# board_4_pg1.net
KiCad netlist of a schematic drawn in Altium Designer
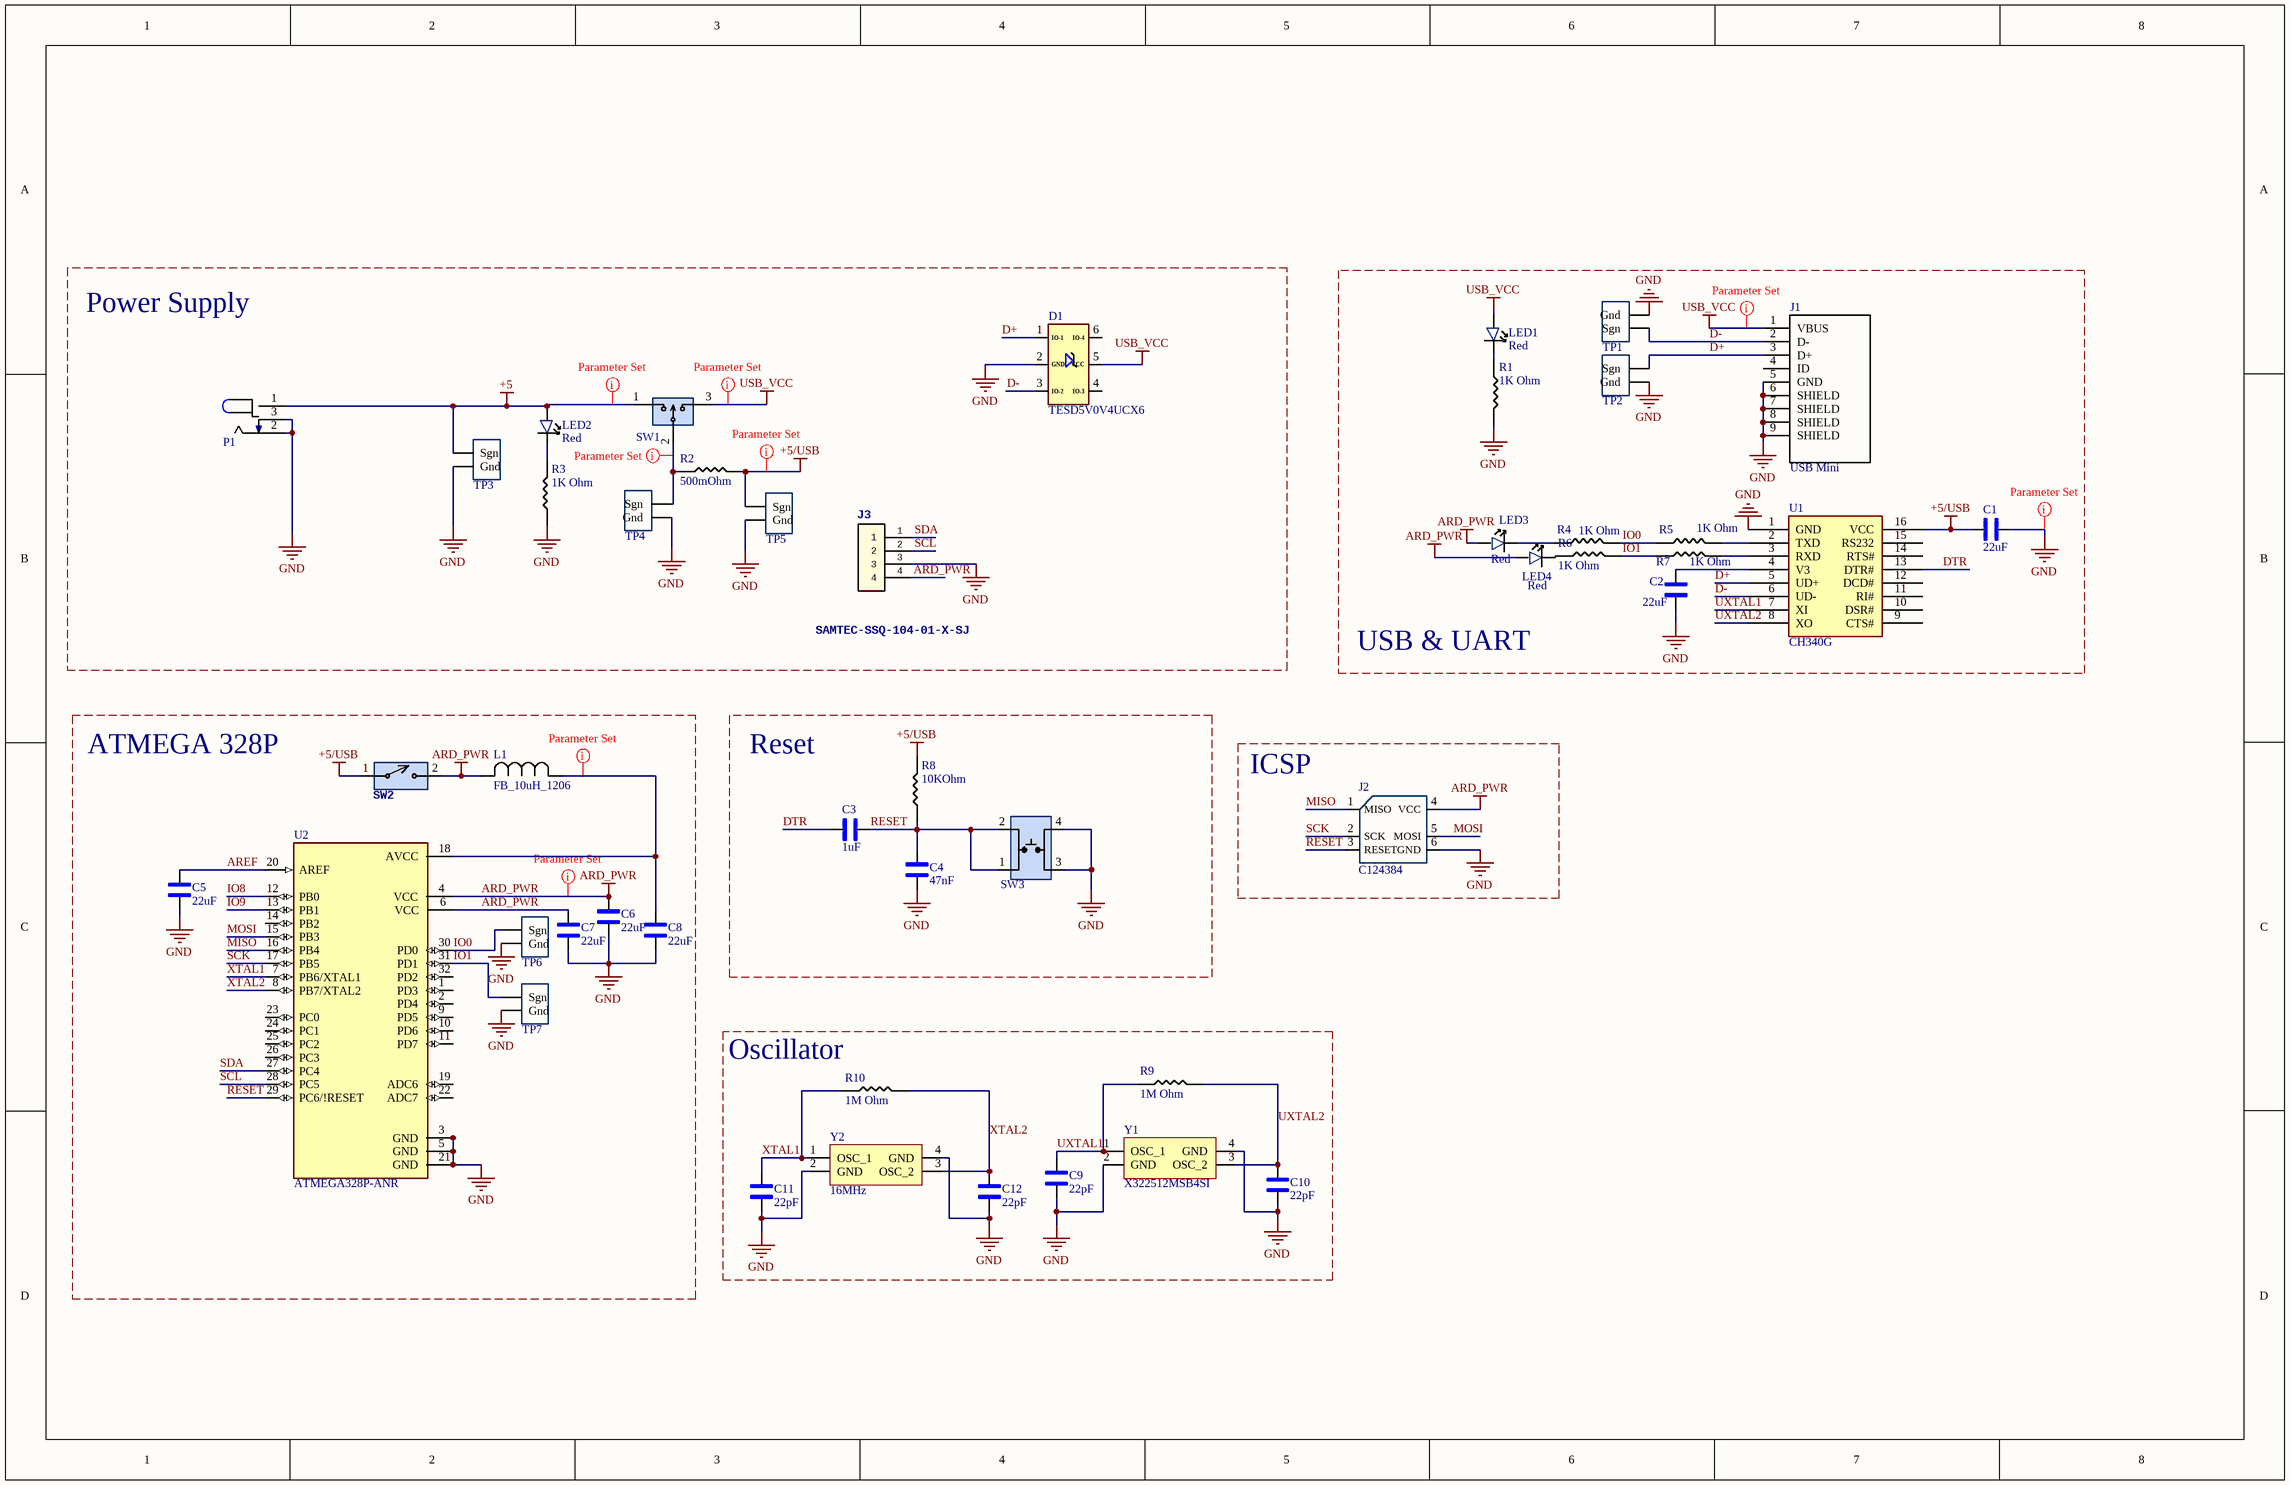
[diagram p0: board_4_pg1.SchDoc]

(export (version "E")
  (design (tool "Eeschema 10.0.6"))
  (components
    (comp (ref "C1")
      (value "22uF")
      (footprint "1206_Passive_Capacitor")
      (description "22uF ±10% 25V X5R 1206 Multilayer Ceramic Capacitors MLCC - SMD/SMT RoHS")
      (fields (field (name "MFR PART #") "CL31A226KAHNNNE") (field (name "LCSC PART#") "C12891"))
      (libsource (lib "ECEN5730Lib_2023_05_DS") (part "C_22uF_1206"))
    )
    (comp (ref "C2")
      (value "22uF")
      (footprint "1206_Passive_Capacitor")
      (description "22uF ±10% 25V X5R 1206 Multilayer Ceramic Capacitors MLCC - SMD/SMT RoHS")
      (fields (field (name "MFR PART #") "CL31A226KAHNNNE") (field (name "LCSC PART#") "C12891"))
      (libsource (lib "ECEN5730Lib_2023_05_DS") (part "C_22uF_1206"))
    )
    (comp (ref "C3")
      (value "1uF")
      (footprint "1206_Passive_Capacitor")
      (description "MULTILAYER CERAMIC CAPACITORS MLCC - SMD/SMT 1UF 50V 1206 ROHS")
      (fields (field (name "MFR PART #") "CL31B105KBHNNNE") (field (name "LCSC PART#") "C1848"))
      (libsource (lib "ECEN5730Lib_2023_05_DS") (part "C_1uF_1206"))
    )
    (comp (ref "C4")
      (value "47nF")
      (footprint "1206_Passive_Capacitor")
      (description "47nF ±5% 50V C0G 1206 Multilayer Ceramic Capacitors MLCC - SMD/SMT RoHS")
      (fields (field (name "LCSC PART#") "C21812") (field (name "MFR PART #") "GRM31M5C1H473JA01L"))
      (libsource (lib "ECEN5730Lib_2023_05_DS") (part "C_47nF_1206"))
    )
    (comp (ref "C5")
      (value "22uF")
      (footprint "1206_Passive_Capacitor")
      (description "22uF ±10% 25V X5R 1206 Multilayer Ceramic Capacitors MLCC - SMD/SMT RoHS")
      (fields (field (name "MFR PART #") "CL31A226KAHNNNE") (field (name "LCSC PART#") "C12891"))
      (libsource (lib "ECEN5730Lib_2023_05_DS") (part "C_22uF_1206"))
    )
    (comp (ref "C6")
      (value "22uF")
      (footprint "1206_Passive_Capacitor")
      (description "22uF ±10% 25V X5R 1206 Multilayer Ceramic Capacitors MLCC - SMD/SMT RoHS")
      (fields (field (name "MFR PART #") "CL31A226KAHNNNE") (field (name "LCSC PART#") "C12891"))
      (libsource (lib "ECEN5730Lib_2023_05_DS") (part "C_22uF_1206"))
    )
    (comp (ref "C7")
      (value "22uF")
      (footprint "1206_Passive_Capacitor")
      (description "22uF ±10% 25V X5R 1206 Multilayer Ceramic Capacitors MLCC - SMD/SMT RoHS")
      (fields (field (name "MFR PART #") "CL31A226KAHNNNE") (field (name "LCSC PART#") "C12891"))
      (libsource (lib "ECEN5730Lib_2023_05_DS") (part "C_22uF_1206"))
    )
    (comp (ref "C8")
      (value "22uF")
      (footprint "1206_Passive_Capacitor")
      (description "22uF ±10% 25V X5R 1206 Multilayer Ceramic Capacitors MLCC - SMD/SMT RoHS")
      (fields (field (name "MFR PART #") "CL31A226KAHNNNE") (field (name "LCSC PART#") "C12891"))
      (libsource (lib "ECEN5730Lib_2023_05_DS") (part "C_22uF_1206"))
    )
    (comp (ref "C9")
      (value "22pF")
      (footprint "1206_Passive_Capacitor")
      (description "22pF ±5% 1kV C0G 1206 Multilayer Ceramic Capacitors MLCC - SMD/SMT RoHS")
      (fields (field (name "LCSC PART#") "C107174") (field (name "MFR PART #") "CC1206JKNPOCBN220"))
      (libsource (lib "ECEN5730Lib_2023_05_DS") (part "C_22pF_1206"))
    )
    (comp (ref "C10")
      (value "22pF")
      (footprint "1206_Passive_Capacitor")
      (description "22pF ±5% 1kV C0G 1206 Multilayer Ceramic Capacitors MLCC - SMD/SMT RoHS")
      (fields (field (name "LCSC PART#") "C107174") (field (name "MFR PART #") "CC1206JKNPOCBN220"))
      (libsource (lib "ECEN5730Lib_2023_05_DS") (part "C_22pF_1206"))
    )
    (comp (ref "C11")
      (value "22pF")
      (footprint "1206_Passive_Capacitor")
      (description "22pF ±5% 1kV C0G 1206 Multilayer Ceramic Capacitors MLCC - SMD/SMT RoHS")
      (fields (field (name "LCSC PART#") "C107174") (field (name "MFR PART #") "CC1206JKNPOCBN220"))
      (libsource (lib "ECEN5730Lib_2023_05_DS") (part "C_22pF_1206"))
    )
    (comp (ref "C12")
      (value "22pF")
      (footprint "1206_Passive_Capacitor")
      (description "22pF ±5% 1kV C0G 1206 Multilayer Ceramic Capacitors MLCC - SMD/SMT RoHS")
      (fields (field (name "LCSC PART#") "C107174") (field (name "MFR PART #") "CC1206JKNPOCBN220"))
      (libsource (lib "ECEN5730Lib_2023_05_DS") (part "C_22pF_1206"))
    )
    (comp (ref "D1")
      (value "TESD5V0V4UCX6")
      (footprint "TVS - TESD")
      (description "TVS SOT-23 ROHS")
      (fields (field (name "LCSC PART#") "C5289077"))
      (libsource (lib "ECEN5730Lib_2023_05_DS_NEW") (part "D_TVS_Diode_TESD"))
    )
    (comp (ref "J1")
      (value "USB Mini")
      (footprint "USB_MINI_B")
      (description "Through Hole USB Connectors RoHS")
      (fields (field (name "LCSC PART#") "C46398") (field (name "MFR PART #") "920-462A2021D10102"))
      (libsource (lib "ECEN5730Lib_2023_05_DS") (part "J_USB_B_Mini"))
    )
    (comp (ref "J2")
      (value "NRPN032PAEN-RC")
      (footprint "ICSP")
      (description "Connector Header Through Hole 6 position 0.079\" (2.00mm)")
      (fields (field (name "LCSC PART#") "C124384"))
      (libsource (lib "ECEN5730Lib_2023_05_DS") (part "J_ICSP"))
    )
    (comp (ref "J3")
      (value "SAMTEC-SSQ-104-01-X-SJ")
      (footprint "JF-4_SSQ-104-01-X-S")
      (fields (field (name "MFR PART #") "SSQ-104-01-X-SJ") (field (name "LCSC PART#") "C2718488"))
      (libsource (lib "ECEN5730Lib_2023_05_DS") (part "JF_4_PIN_FEMALE"))
    )
    (comp (ref "L1")
      (value "FB_10uH_1206")
      (footprint "AIML-1206_ABR-M")
      (description "25mA 10uH ±10% 800mΩ 1206  Inductors (SMD) ROHS")
      (fields (field (name "MFR PART #") "CMI321609X100KT") (field (name "LCSC PART#") "C1051"))
      (libsource (lib "ECEN5730Lib_2023_05_DS") (part "FB_10uH_1206"))
    )
    (comp (ref "LED1")
      (value "Red")
      (footprint "LED_1206")
      (description "Red 621~631nm 1206 Light Emitting Diodes (LED) RoHS")
      (fields (field (name "MFR PART #") "15-21/R6C-FQ1R1B/2T") (field (name "LCSC PART#") "C93133"))
      (libsource (lib "ECEN5730Lib_2023_05_DS") (part "LED_RED_1206"))
    )
    (comp (ref "LED2")
      (value "Red")
      (footprint "LED_1206")
      (description "Red 621~631nm 1206 Light Emitting Diodes (LED) RoHS")
      (fields (field (name "MFR PART #") "15-21/R6C-FQ1R1B/2T") (field (name "LCSC PART#") "C93133"))
      (libsource (lib "ECEN5730Lib_2023_05_DS") (part "LED_RED_1206"))
    )
    (comp (ref "LED3")
      (value "Red")
      (footprint "LED_1206")
      (description "Red 621~631nm 1206 Light Emitting Diodes (LED) RoHS")
      (fields (field (name "MFR PART #") "15-21/R6C-FQ1R1B/2T") (field (name "LCSC PART#") "C93133"))
      (libsource (lib "ECEN5730Lib_2023_05_DS") (part "LED_RED_1206"))
    )
    (comp (ref "LED4")
      (value "Red")
      (footprint "LED_1206")
      (description "Red 621~631nm 1206 Light Emitting Diodes (LED) RoHS")
      (fields (field (name "MFR PART #") "15-21/R6C-FQ1R1B/2T") (field (name "LCSC PART#") "C93133"))
      (libsource (lib "ECEN5730Lib_2023_05_DS") (part "LED_RED_1206"))
    )
    (comp (ref "P1")
      (value "Power Jack")
      (footprint "Power_Jack")
      (description "Power Barrel Connector Jack 2.10mm ID (0.083\"), 5.50mm OD (0.217\") Through Hole, Right Angle")
      (fields (field (name "MFR PART #") "PJ-102A") (field (name "LCSC PART#") "C136744"))
      (libsource (lib "ECEN5730Lib_2023_05_DS") (part "P_Power Jack"))
    )
    (comp (ref "R1")
      (value "1K Ohm")
      (footprint "1206_Passive_Resitor")
      (description "CHIP RESISTOR - SURFACE MOUNT 1KOHMS ±1% 1/4W 1206 ROHS")
      (fields (field (name "MFR PART #") "RNCP1206FTD1K00CT") (field (name "LCSC PART#") "C4410"))
      (libsource (lib "ECEN5730Lib_2023_05_DS") (part "R_1K_1206"))
    )
    (comp (ref "R2")
      (value "500mOhm")
      (footprint "1206_Passive_Resitor")
      (description "Resistors/Shunt 250mW 500mΩ ±800ppm/℃ ±5% 1206  Current Sense  Resistors ROHS")
      (fields (field (name "MFR PART #") "1206W4J050KT5E") (field (name "LCSC PART#") "C247433"))
      (libsource (lib "ECEN5730Lib_2023_05_DS") (part "R_500mOhm_1206"))
    )
    (comp (ref "R3")
      (value "1K Ohm")
      (footprint "1206_Passive_Resitor")
      (description "CHIP RESISTOR - SURFACE MOUNT 1KOHMS ±1% 1/4W 1206 ROHS")
      (fields (field (name "MFR PART #") "RNCP1206FTD1K00CT") (field (name "LCSC PART#") "C4410"))
      (libsource (lib "ECEN5730Lib_2023_05_DS") (part "R_1K_1206"))
    )
    (comp (ref "R4")
      (value "1K Ohm")
      (footprint "1206_Passive_Resitor")
      (description "CHIP RESISTOR - SURFACE MOUNT 1KOHMS ±1% 1/4W 1206 ROHS")
      (fields (field (name "MFR PART #") "RNCP1206FTD1K00CT") (field (name "LCSC PART#") "C4410"))
      (libsource (lib "ECEN5730Lib_2023_05_DS") (part "R_1K_1206"))
    )
    (comp (ref "R5")
      (value "1K Ohm")
      (footprint "1206_Passive_Resitor")
      (description "CHIP RESISTOR - SURFACE MOUNT 1KOHMS ±1% 1/4W 1206 ROHS")
      (fields (field (name "MFR PART #") "RNCP1206FTD1K00CT") (field (name "LCSC PART#") "C4410"))
      (libsource (lib "ECEN5730Lib_2023_05_DS") (part "R_1K_1206"))
    )
    (comp (ref "R6")
      (value "1K Ohm")
      (footprint "1206_Passive_Resitor")
      (description "CHIP RESISTOR - SURFACE MOUNT 1KOHMS ±1% 1/4W 1206 ROHS")
      (fields (field (name "MFR PART #") "RNCP1206FTD1K00CT") (field (name "LCSC PART#") "C4410"))
      (libsource (lib "ECEN5730Lib_2023_05_DS") (part "R_1K_1206"))
    )
    (comp (ref "R7")
      (value "1K Ohm")
      (footprint "1206_Passive_Resitor")
      (description "CHIP RESISTOR - SURFACE MOUNT 1KOHMS ±1% 1/4W 1206 ROHS")
      (fields (field (name "MFR PART #") "RNCP1206FTD1K00CT") (field (name "LCSC PART#") "C4410"))
      (libsource (lib "ECEN5730Lib_2023_05_DS") (part "R_1K_1206"))
    )
    (comp (ref "R8")
      (value "10KOhm")
      (footprint "1206_Passive_Resitor")
      (description "10 kOhms ±5% 0.25W, 1/4W Chip Resistor 1206 (3216 Metric) Automotive AEC-Q200 Thick Film")
      (fields (field (name "MFR PART #") "RMCF1206FT10K0") (field (name "LCSC PART#") "C17902"))
      (libsource (lib "ECEN5730Lib_2023_05_DS") (part "R_10KOhm_1206"))
    )
    (comp (ref "R9")
      (value "1M Ohm")
      (footprint "1206_Passive_Resitor")
      (description "CHIP RESISTOR - SURFACE MOUNT 1MOHMS ±1% 1/4W 1206 ROHS")
      (fields (field (name "MFR PART #") "RMCF1206JT1M00") (field (name "LCSC PART#") "C17927"))
      (libsource (lib "ECEN5730Lib_2023_05_DS") (part "R_1M_1206"))
    )
    (comp (ref "R10")
      (value "1M Ohm")
      (footprint "1206_Passive_Resitor")
      (description "CHIP RESISTOR - SURFACE MOUNT 1MOHMS ±1% 1/4W 1206 ROHS")
      (fields (field (name "MFR PART #") "RMCF1206JT1M00") (field (name "LCSC PART#") "C17927"))
      (libsource (lib "ECEN5730Lib_2023_05_DS") (part "R_1M_1206"))
    )
    (comp (ref "SW1")
      (value "PREC003SAAN-RC")
      (footprint "3_PIN_100mil")
      (description "Connector Header Through Hole 3 position 0.100\" (2.54mm)")
      (fields (field (name "LCSC PART#") "C49257"))
      (libsource (lib "ECEN5730Lib_2023_05_DS") (part "SW_3Pin_100mil_Switch"))
    )
    (comp (ref "SW2")
      (value "SW_2Pin_100mil_Switch")
      (footprint "2Pin-Header-Conn")
      (description "2Pin Header")
      (fields (field (name "LCSC PART#") "C124375"))
      (libsource (lib "ECEN5730Lib_2023_05_DS") (part "SW_2Pin_100mil_Switch"))
    )
    (comp (ref "SW3")
      (value "TL3305AF160QG")
      (footprint "Switch_JLC")
      (description "Tactile Switch SPST-NO Top Actuated Surface Mount")
      (fields (field (name "MFR PART #") "KH-4.5X4.5X4.3H-STM") (field (name "LCSC PART#") "C2837550"))
      (libsource (lib "ECEN5730Lib_2023_05_DS") (part "SW_Push_Button_JLC"))
    )
    (comp (ref "TP1")
      (value "10x Probe TP")
      (footprint "TP10x_Probe")
      (description "Test Point 300 mil centers")
      (libsource (lib "ECEN5730Lib_2023_05_DS") (part "TP_10x_Probe"))
    )
    (comp (ref "TP2")
      (value "10x Probe TP")
      (footprint "TP10x_Probe")
      (description "Test Point 300 mil centers")
      (libsource (lib "") (part "TP_10x_Probe_2"))
    )
    (comp (ref "TP3")
      (value "10x Probe TP")
      (footprint "TP10x_Probe")
      (description "Test Point 300 mil centers")
      (libsource (lib "") (part "TP_10x_Probe_1"))
    )
    (comp (ref "TP4")
      (value "10x Probe TP")
      (footprint "TP10x_Probe")
      (description "Test Point 300 mil centers")
      (libsource (lib "") (part "TP_10x_Probe_2"))
    )
    (comp (ref "TP5")
      (value "10x Probe TP")
      (footprint "TP10x_Probe")
      (description "Test Point 300 mil centers")
      (libsource (lib "") (part "TP_10x_Probe_1"))
    )
    (comp (ref "TP6")
      (value "10x Probe TP")
      (footprint "TP10x_Probe")
      (description "Test Point 300 mil centers")
      (libsource (lib "") (part "TP_10x_Probe_1"))
    )
    (comp (ref "TP7")
      (value "10x Probe TP")
      (footprint "TP10x_Probe")
      (description "Test Point 300 mil centers")
      (libsource (lib "") (part "TP_10x_Probe_1"))
    )
    (comp (ref "U1")
      (value "CH340G")
      (footprint "USB to serial")
      (description "Transceiver USB 2.0 2Mbps SOP-16_150mil USB ICs RoHS")
      (fields (field (name "LCSC PART#") "C14267"))
      (libsource (lib "ECEN5730Lib_2023_05_DS") (part "U_USBtoSerial"))
    )
    (comp (ref "U2")
      (value "ATMEGA328P-ANR")
      (footprint "ATMega328P")
      (description "AVR AVR® ATmega Microcontroller IC 8-Bit 20MHz 32KB (16K x 16) FLASH 32-TQFP (7x7)")
      (fields (field (name "MFR PART #") "ATMEGA328P-AU") (field (name "LCSC PART#") "C14877"))
      (libsource (lib "ECEN5730Lib_2023_05_DS") (part "U_ATMega328P"))
    )
    (comp (ref "Y1")
      (value "X322512MSB4SI")
      (footprint "Crystal resonator")
      (description "SMD Crystal Resonators 12MHz ±10ppm SMD-3225_4P RoHS")
      (fields (field (name "LCSC PART#") "C9002"))
      (libsource (lib "ECEN5730Lib_2023_05_DS") (part "X_12MHz_Res"))
    )
    (comp (ref "Y2")
      (value "16MHz")
      (footprint "Crystal resonator")
      (description "±10ppm 16000000Hz -40℃~85℃ 贴片无源晶振 60Ω 9pF SMD3225-4P Crystals ROHS")
      (fields (field (name "LCSC PART#") "C13738") (field (name "MFR PART #") "X322516MLB4SI"))
      (libsource (lib "ECEN5730Lib_2023_05_DS") (part "X_16Mhz_Res"))
    )
  )
  (nets
    (net (code "1") (name "+5") (class "Default")
      (node (ref "LED2") (pin "1") (pinfunction "1_1") (pintype "passive"))
      (node (ref "P1") (pin "1") (pinfunction "1_1") (pintype "power_in"))
      (node (ref "SW1") (pin "1") (pinfunction "1_1") (pintype "passive"))
      (node (ref "TP3") (pin "1") (pinfunction "Sgn_1") (pintype "passive"))
    )
    (net (code "2") (name "+5{slash}USB") (class "Default")
      (node (ref "C1") (pin "1") (pinfunction "1_1") (pintype "passive"))
      (node (ref "R2") (pin "2") (pinfunction "2_2") (pintype "passive"))
      (node (ref "R8") (pin "2") (pinfunction "2_2") (pintype "passive"))
      (node (ref "SW2") (pin "1") (pinfunction "1_1") (pintype "passive"))
      (node (ref "TP5") (pin "1") (pinfunction "Sgn_1") (pintype "passive"))
      (node (ref "U1") (pin "16") (pinfunction "VCC_16") (pintype "passive"))
    )
    (net (code "3") (name "/AREF") (class "Default")
      (node (ref "C5") (pin "1") (pinfunction "1_1") (pintype "passive"))
      (node (ref "U2") (pin "20") (pinfunction "AREF_20") (pintype "input"))
    )
    (net (code "4") (name "/D+") (class "Default")
      (node (ref "D1") (pin "1") (pinfunction "IO-1_1") (pintype "passive"))
      (node (ref "J1") (pin "3") (pinfunction "D+_3") (pintype "passive"))
      (node (ref "TP2") (pin "1") (pinfunction "Sgn_1") (pintype "passive"))
      (node (ref "U1") (pin "5") (pinfunction "UD+_5") (pintype "passive"))
    )
    (net (code "5") (name "/D-") (class "Default")
      (node (ref "D1") (pin "3") (pinfunction "IO-2_3") (pintype "passive"))
      (node (ref "J1") (pin "2") (pinfunction "D-_2") (pintype "passive"))
      (node (ref "TP1") (pin "1") (pinfunction "Sgn_1") (pintype "passive"))
      (node (ref "U1") (pin "6") (pinfunction "UD-_6") (pintype "passive"))
    )
    (net (code "6") (name "/DTR") (class "Default")
      (node (ref "C3") (pin "1") (pinfunction "1_1") (pintype "passive"))
      (node (ref "U1") (pin "13") (pinfunction "DTR#_13") (pintype "passive"))
    )
    (net (code "7") (name "/IO0") (class "Default")
      (node (ref "R4") (pin "2") (pinfunction "2_2") (pintype "passive"))
      (node (ref "R5") (pin "1") (pinfunction "1_1") (pintype "passive"))
      (node (ref "TP6") (pin "1") (pinfunction "Sgn_1") (pintype "passive"))
      (node (ref "U2") (pin "30") (pinfunction "PD0_30") (pintype "bidirectional"))
    )
    (net (code "8") (name "/IO1") (class "Default")
      (node (ref "R6") (pin "2") (pinfunction "2_2") (pintype "passive"))
      (node (ref "R7") (pin "1") (pinfunction "1_1") (pintype "passive"))
      (node (ref "TP7") (pin "1") (pinfunction "Sgn_1") (pintype "passive"))
      (node (ref "U2") (pin "31") (pinfunction "PD1_31") (pintype "bidirectional"))
    )
    (net (code "9") (name "/IO8") (class "Default")
      (node (ref "U2") (pin "12") (pinfunction "PB0_12") (pintype "bidirectional"))
    )
    (net (code "10") (name "/IO9") (class "Default")
      (node (ref "U2") (pin "13") (pinfunction "PB1_13") (pintype "bidirectional"))
    )
    (net (code "11") (name "/MISO") (class "Default")
      (node (ref "J2") (pin "1") (pinfunction "MISO_1") (pintype "passive"))
      (node (ref "U2") (pin "16") (pinfunction "PB4_16") (pintype "bidirectional"))
    )
    (net (code "12") (name "/MOSI") (class "Default")
      (node (ref "J2") (pin "5") (pinfunction "MOSI_5") (pintype "passive"))
      (node (ref "U2") (pin "15") (pinfunction "PB3_15") (pintype "bidirectional"))
    )
    (net (code "13") (name "/RESET") (class "Default")
      (node (ref "C3") (pin "2") (pinfunction "2_2") (pintype "passive"))
      (node (ref "C4") (pin "2") (pinfunction "2_2") (pintype "passive"))
      (node (ref "J2") (pin "3") (pinfunction "RESET_3") (pintype "passive"))
      (node (ref "R8") (pin "1") (pinfunction "1_1") (pintype "passive"))
      (node (ref "SW3") (pin "1") (pinfunction "1_1") (pintype "passive"))
      (node (ref "SW3") (pin "2") (pinfunction "2_2") (pintype "passive"))
      (node (ref "U2") (pin "29") (pinfunction "PC6/!RESET_29") (pintype "bidirectional"))
    )
    (net (code "14") (name "/SCK") (class "Default")
      (node (ref "J2") (pin "2") (pinfunction "SCK_2") (pintype "passive"))
      (node (ref "U2") (pin "17") (pinfunction "PB5_17") (pintype "bidirectional"))
    )
    (net (code "15") (name "/SCL") (class "Default")
      (node (ref "J3") (pin "2") (pinfunction "2_2") (pintype "passive"))
      (node (ref "U2") (pin "28") (pinfunction "PC5_28") (pintype "bidirectional"))
    )
    (net (code "16") (name "/SDA") (class "Default")
      (node (ref "J3") (pin "1") (pinfunction "1_1") (pintype "passive"))
      (node (ref "U2") (pin "27") (pinfunction "PC4_27") (pintype "bidirectional"))
    )
    (net (code "17") (name "/UXTAL1") (class "Default")
      (node (ref "C9") (pin "2") (pinfunction "2_2") (pintype "passive"))
      (node (ref "R9") (pin "1") (pinfunction "1_1") (pintype "passive"))
      (node (ref "U1") (pin "7") (pinfunction "XI_7") (pintype "passive"))
      (node (ref "Y1") (pin "1") (pinfunction "OSC_1_1") (pintype "passive"))
    )
    (net (code "18") (name "/UXTAL2") (class "Default")
      (node (ref "C10") (pin "2") (pinfunction "2_2") (pintype "passive"))
      (node (ref "R9") (pin "2") (pinfunction "2_2") (pintype "passive"))
      (node (ref "U1") (pin "8") (pinfunction "XO_8") (pintype "passive"))
      (node (ref "Y1") (pin "3") (pinfunction "OSC_2_3") (pintype "passive"))
    )
    (net (code "19") (name "/XTAL1") (class "Default")
      (node (ref "C11") (pin "2") (pinfunction "2_2") (pintype "passive"))
      (node (ref "R10") (pin "1") (pinfunction "1_1") (pintype "passive"))
      (node (ref "U2") (pin "7") (pinfunction "PB6/XTAL1_7") (pintype "bidirectional"))
      (node (ref "Y2") (pin "1") (pinfunction "OSC_1_1") (pintype "passive"))
    )
    (net (code "20") (name "/XTAL2") (class "Default")
      (node (ref "C12") (pin "2") (pinfunction "2_2") (pintype "passive"))
      (node (ref "R10") (pin "2") (pinfunction "2_2") (pintype "passive"))
      (node (ref "U2") (pin "8") (pinfunction "PB7/XTAL2_8") (pintype "bidirectional"))
      (node (ref "Y2") (pin "3") (pinfunction "OSC_2_3") (pintype "passive"))
    )
    (net (code "21") (name "ARD_PWR") (class "Default")
      (node (ref "C6") (pin "1") (pinfunction "1_1") (pintype "passive"))
      (node (ref "C7") (pin "1") (pinfunction "1_1") (pintype "passive"))
      (node (ref "J2") (pin "4") (pinfunction "VCC_4") (pintype "passive"))
      (node (ref "J3") (pin "4") (pinfunction "4_4") (pintype "passive"))
      (node (ref "L1") (pin "2") (pinfunction "2_2") (pintype "passive"))
      (node (ref "LED3") (pin "1") (pinfunction "1_1") (pintype "passive"))
      (node (ref "LED4") (pin "1") (pinfunction "1_1") (pintype "passive"))
      (node (ref "SW2") (pin "2") (pinfunction "2_2") (pintype "passive"))
      (node (ref "U2") (pin "4") (pinfunction "VCC_4") (pintype "power_in"))
      (node (ref "U2") (pin "6") (pinfunction "VCC_6") (pintype "power_in"))
    )
    (net (code "22") (name "GND") (class "Default")
      (node (ref "C1") (pin "2") (pinfunction "2_2") (pintype "passive"))
      (node (ref "C10") (pin "1") (pinfunction "1_1") (pintype "passive"))
      (node (ref "C11") (pin "1") (pinfunction "1_1") (pintype "passive"))
      (node (ref "C12") (pin "1") (pinfunction "1_1") (pintype "passive"))
      (node (ref "C2") (pin "2") (pinfunction "2_2") (pintype "passive"))
      (node (ref "C4") (pin "1") (pinfunction "1_1") (pintype "passive"))
      (node (ref "C5") (pin "2") (pinfunction "2_2") (pintype "passive"))
      (node (ref "C6") (pin "2") (pinfunction "2_2") (pintype "passive"))
      (node (ref "C7") (pin "2") (pinfunction "2_2") (pintype "passive"))
      (node (ref "C8") (pin "2") (pinfunction "2_2") (pintype "passive"))
      (node (ref "C9") (pin "1") (pinfunction "1_1") (pintype "passive"))
      (node (ref "D1") (pin "2") (pinfunction "GND_2") (pintype "passive"))
      (node (ref "J1") (pin "5") (pinfunction "GND_5") (pintype "passive"))
      (node (ref "J1") (pin "6") (pinfunction "SHIELD_6") (pintype "passive"))
      (node (ref "J1") (pin "7") (pinfunction "SHIELD_7") (pintype "passive"))
      (node (ref "J1") (pin "8") (pinfunction "SHIELD_8") (pintype "passive"))
      (node (ref "J1") (pin "9") (pinfunction "SHIELD_9") (pintype "passive"))
      (node (ref "J2") (pin "6") (pinfunction "GND_6") (pintype "passive"))
      (node (ref "J3") (pin "3") (pinfunction "3_3") (pintype "passive"))
      (node (ref "P1") (pin "2") (pinfunction "2_2") (pintype "power_in"))
      (node (ref "P1") (pin "3") (pinfunction "3_3") (pintype "power_in"))
      (node (ref "R1") (pin "2") (pinfunction "2_2") (pintype "passive"))
      (node (ref "R3") (pin "1") (pinfunction "1_1") (pintype "passive"))
      (node (ref "SW3") (pin "3") (pinfunction "3_3") (pintype "passive"))
      (node (ref "SW3") (pin "4") (pinfunction "4_4") (pintype "passive"))
      (node (ref "TP1") (pin "2") (pinfunction "Gnd_2") (pintype "passive"))
      (node (ref "TP2") (pin "2") (pinfunction "Gnd_2") (pintype "passive"))
      (node (ref "TP3") (pin "2") (pinfunction "Gnd_2") (pintype "passive"))
      (node (ref "TP4") (pin "2") (pinfunction "Gnd_2") (pintype "passive"))
      (node (ref "TP5") (pin "2") (pinfunction "Gnd_2") (pintype "passive"))
      (node (ref "TP6") (pin "2") (pinfunction "Gnd_2") (pintype "passive"))
      (node (ref "TP7") (pin "2") (pinfunction "Gnd_2") (pintype "passive"))
      (node (ref "U1") (pin "1") (pinfunction "GND_1") (pintype "passive"))
      (node (ref "U2") (pin "21") (pinfunction "GND_21") (pintype "power_in"))
      (node (ref "U2") (pin "3") (pinfunction "GND_3") (pintype "power_in"))
      (node (ref "U2") (pin "5") (pinfunction "GND_5") (pintype "power_in"))
      (node (ref "Y1") (pin "2") (pinfunction "GND_2") (pintype "passive"))
      (node (ref "Y1") (pin "4") (pinfunction "GND_4") (pintype "passive"))
      (node (ref "Y2") (pin "2") (pinfunction "GND_2") (pintype "passive"))
      (node (ref "Y2") (pin "4") (pinfunction "GND_4") (pintype "passive"))
    )
    (net (code "23") (name "Net-(LED1-Pad2)") (class "Default")
      (node (ref "LED1") (pin "2") (pinfunction "2_2") (pintype "passive"))
      (node (ref "R1") (pin "1") (pinfunction "1_1") (pintype "passive"))
    )
    (net (code "24") (name "Net-(LED2-Pad2)") (class "Default")
      (node (ref "LED2") (pin "2") (pinfunction "2_2") (pintype "passive"))
      (node (ref "R3") (pin "2") (pinfunction "2_2") (pintype "passive"))
    )
    (net (code "25") (name "Net-(LED3-Pad2)") (class "Default")
      (node (ref "LED3") (pin "2") (pinfunction "2_2") (pintype "passive"))
      (node (ref "R4") (pin "1") (pinfunction "1_1") (pintype "passive"))
    )
    (net (code "26") (name "Net-(LED4-Pad2)") (class "Default")
      (node (ref "LED4") (pin "2") (pinfunction "2_2") (pintype "passive"))
      (node (ref "R6") (pin "1") (pinfunction "1_1") (pintype "passive"))
    )
    (net (code "27") (name "Net-(TP4-Sgn)") (class "Default")
      (node (ref "R2") (pin "1") (pinfunction "1_1") (pintype "passive"))
      (node (ref "SW1") (pin "2") (pinfunction "2_2") (pintype "passive"))
      (node (ref "TP4") (pin "1") (pinfunction "Sgn_1") (pintype "passive"))
    )
    (net (code "28") (name "Net-(U1-RXD)") (class "Default")
      (node (ref "R7") (pin "2") (pinfunction "2_2") (pintype "passive"))
      (node (ref "U1") (pin "3") (pinfunction "RXD_3") (pintype "passive"))
    )
    (net (code "29") (name "Net-(U1-TXD)") (class "Default")
      (node (ref "R5") (pin "2") (pinfunction "2_2") (pintype "passive"))
      (node (ref "U1") (pin "2") (pinfunction "TXD_2") (pintype "passive"))
    )
    (net (code "30") (name "Net-(U1-V3)") (class "Default")
      (node (ref "C2") (pin "1") (pinfunction "1_1") (pintype "passive"))
      (node (ref "U1") (pin "4") (pinfunction "V3_4") (pintype "passive"))
    )
    (net (code "31") (name "Net-(U2-AVCC)") (class "Default")
      (node (ref "C8") (pin "1") (pinfunction "1_1") (pintype "passive"))
      (node (ref "L1") (pin "1") (pinfunction "1_1") (pintype "passive"))
      (node (ref "U2") (pin "18") (pinfunction "AVCC_18") (pintype "power_in"))
    )
    (net (code "32") (name "USB_VCC") (class "Default")
      (node (ref "D1") (pin "5") (pinfunction "VCC_5") (pintype "passive"))
      (node (ref "J1") (pin "1") (pinfunction "VBUS_1") (pintype "passive"))
      (node (ref "LED1") (pin "1") (pinfunction "1_1") (pintype "passive"))
      (node (ref "SW1") (pin "3") (pinfunction "3_3") (pintype "passive"))
    )
    (net (code "33") (name "unconnected-(D1-IO-3-Pad4)") (class "Default")
      (node (ref "D1") (pin "4") (pinfunction "IO-3_4") (pintype "passive"))
    )
    (net (code "34") (name "unconnected-(D1-IO-4-Pad6)") (class "Default")
      (node (ref "D1") (pin "6") (pinfunction "IO-4_6") (pintype "passive"))
    )
    (net (code "35") (name "unconnected-(J1-ID-Pad4)") (class "Default")
      (node (ref "J1") (pin "4") (pinfunction "ID_4") (pintype "passive"))
    )
    (net (code "36") (name "unconnected-(U1-CTS#-Pad9)") (class "Default")
      (node (ref "U1") (pin "9") (pinfunction "CTS#_9") (pintype "passive"))
    )
    (net (code "37") (name "unconnected-(U1-DCD#-Pad12)") (class "Default")
      (node (ref "U1") (pin "12") (pinfunction "DCD#_12") (pintype "passive"))
    )
    (net (code "38") (name "unconnected-(U1-DSR#-Pad10)") (class "Default")
      (node (ref "U1") (pin "10") (pinfunction "DSR#_10") (pintype "passive"))
    )
    (net (code "39") (name "unconnected-(U1-RI#-Pad11)") (class "Default")
      (node (ref "U1") (pin "11") (pinfunction "RI#_11") (pintype "passive"))
    )
    (net (code "40") (name "unconnected-(U1-RS232-Pad15)") (class "Default")
      (node (ref "U1") (pin "15") (pinfunction "RS232_15") (pintype "passive"))
    )
    (net (code "41") (name "unconnected-(U1-RTS#-Pad14)") (class "Default")
      (node (ref "U1") (pin "14") (pinfunction "RTS#_14") (pintype "passive"))
    )
    (net (code "42") (name "unconnected-(U2-ADC6-Pad19)") (class "Default")
      (node (ref "U2") (pin "19") (pinfunction "ADC6_19") (pintype "bidirectional"))
    )
    (net (code "43") (name "unconnected-(U2-ADC7-Pad22)") (class "Default")
      (node (ref "U2") (pin "22") (pinfunction "ADC7_22") (pintype "bidirectional"))
    )
    (net (code "44") (name "unconnected-(U2-PB2-Pad14)") (class "Default")
      (node (ref "U2") (pin "14") (pinfunction "PB2_14") (pintype "bidirectional"))
    )
    (net (code "45") (name "unconnected-(U2-PC0-Pad23)") (class "Default")
      (node (ref "U2") (pin "23") (pinfunction "PC0_23") (pintype "bidirectional"))
    )
    (net (code "46") (name "unconnected-(U2-PC1-Pad24)") (class "Default")
      (node (ref "U2") (pin "24") (pinfunction "PC1_24") (pintype "bidirectional"))
    )
    (net (code "47") (name "unconnected-(U2-PC2-Pad25)") (class "Default")
      (node (ref "U2") (pin "25") (pinfunction "PC2_25") (pintype "bidirectional"))
    )
    (net (code "48") (name "unconnected-(U2-PC3-Pad26)") (class "Default")
      (node (ref "U2") (pin "26") (pinfunction "PC3_26") (pintype "bidirectional"))
    )
    (net (code "49") (name "unconnected-(U2-PD2-Pad32)") (class "Default")
      (node (ref "U2") (pin "32") (pinfunction "PD2_32") (pintype "bidirectional"))
    )
    (net (code "50") (name "unconnected-(U2-PD3-Pad1)") (class "Default")
      (node (ref "U2") (pin "1") (pinfunction "PD3_1") (pintype "bidirectional"))
    )
    (net (code "51") (name "unconnected-(U2-PD4-Pad2)") (class "Default")
      (node (ref "U2") (pin "2") (pinfunction "PD4_2") (pintype "bidirectional"))
    )
    (net (code "52") (name "unconnected-(U2-PD5-Pad9)") (class "Default")
      (node (ref "U2") (pin "9") (pinfunction "PD5_9") (pintype "bidirectional"))
    )
    (net (code "53") (name "unconnected-(U2-PD6-Pad10)") (class "Default")
      (node (ref "U2") (pin "10") (pinfunction "PD6_10") (pintype "bidirectional"))
    )
    (net (code "54") (name "unconnected-(U2-PD7-Pad11)") (class "Default")
      (node (ref "U2") (pin "11") (pinfunction "PD7_11") (pintype "bidirectional"))
    )
  )
)
